# FIT2017_Uno_Shield.net
KiCad netlist of a schematic drawn in Altium Designer
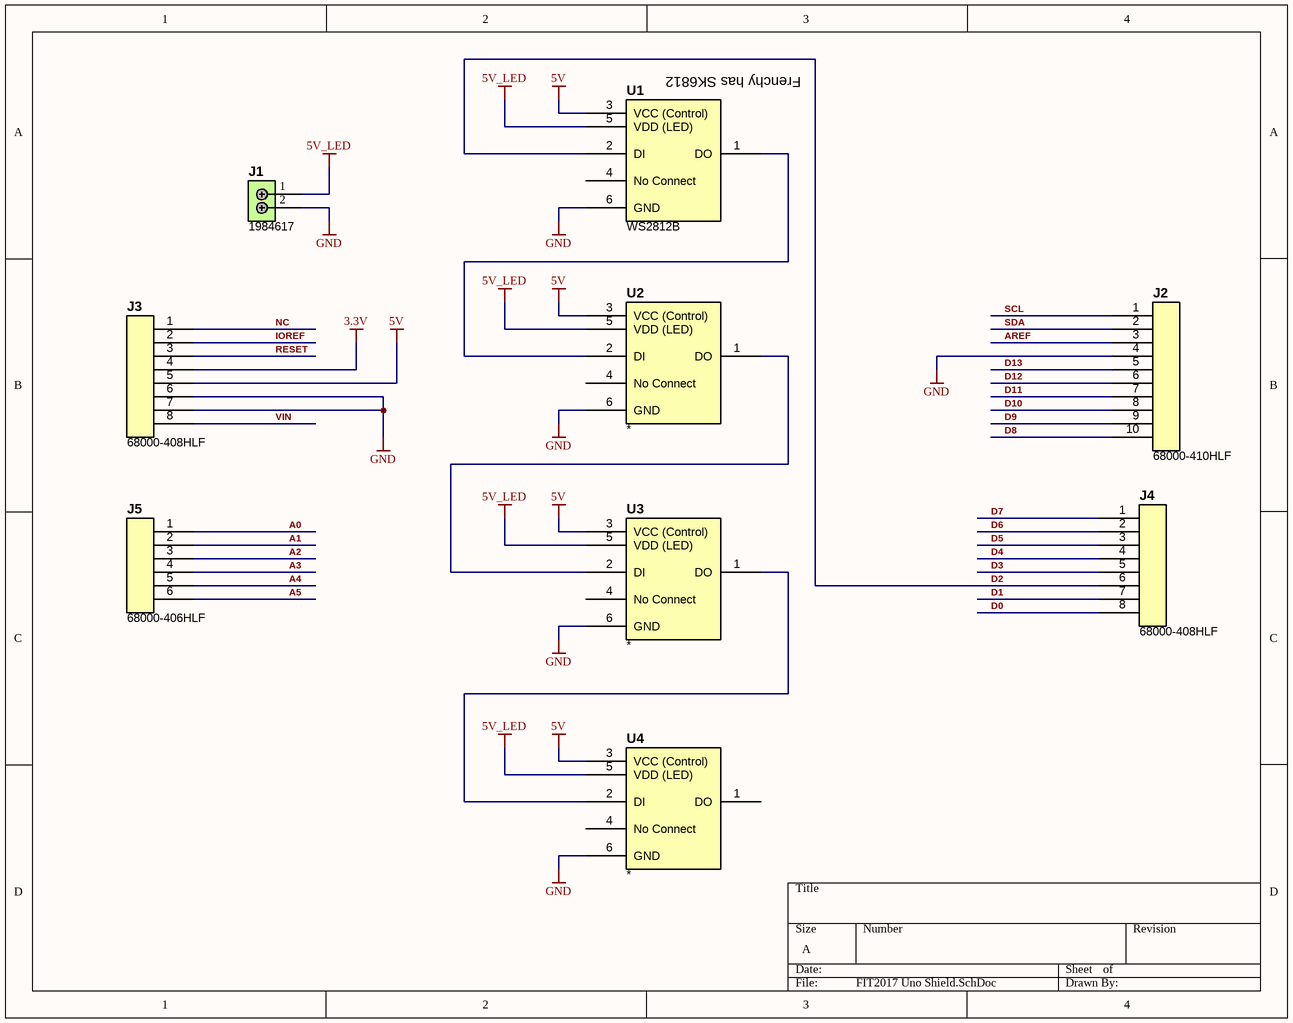
[diagram p0: FIT2017 Uno Shield.SchDoc]

(export (version "E")
  (design (tool "Eeschema 10.0.6"))
  (components
    (comp (ref "J1")
      (value "1984617")
      (footprint "1984617")
      (description "CONN TERM BLOCK T/H 2POS 3.5MM")
      (fields (field (name "MANUFACTURER") "Phoenix Contact") (field (name "VOLTAGE") "300V"))
      (libsource (lib "FIT2017_UnoShield") (part "1984617"))
    )
    (comp (ref "J2")
      (value "68000-410HLF")
      (footprint "68000-410HLF_Bottom Mount")
      (description "10 Positions Header, Unshrouded Connector 0.100\" (2.54mm) Through Hole Tin")
      (fields (field (name "MANUFACTURER") "Amphenol FCI"))
      (libsource (lib "FIT2017_UnoShield") (part "68000-410HLF"))
    )
    (comp (ref "J3")
      (value "68000-408HLF")
      (footprint "68000-408HLF_Bottom Mount")
      (description "CONN HEADER 8POS .100 STR TIN")
      (fields (field (name "MANUFACTURER") "Amphenol FCI"))
      (libsource (lib "FIT2017_UnoShield") (part "68000-408HLF"))
    )
    (comp (ref "J4")
      (value "68000-408HLF")
      (footprint "68000-408HLF_Bottom Mount")
      (description "CONN HEADER 8POS .100 STR TIN")
      (fields (field (name "MANUFACTURER") "Amphenol FCI"))
      (libsource (lib "") (part "68000-408HLF_1"))
    )
    (comp (ref "J5")
      (value "68000-406HLF")
      (footprint "68000-406HLF_Bottom Mount")
      (description "CONN HEADER 6POS .100 STR TIN")
      (fields (field (name "MANUFACTURER") "Amphenol FCI"))
      (libsource (lib "FIT2017_UnoShield") (part "68000-406HLF"))
    )
    (comp (ref "U1")
      (value "WS2812B")
      (footprint "WS2812")
      (libsource (lib "FIT2017_UnoShield") (part "WS2812"))
    )
    (comp (ref "U2") (value "*") (footprint "WS2812") (libsource (lib "FIT2017_UnoShield") (part "WS2812")))
    (comp (ref "U3") (value "*") (footprint "WS2812") (libsource (lib "FIT2017_UnoShield") (part "WS2812")))
    (comp (ref "U4") (value "*") (footprint "WS2812") (libsource (lib "FIT2017_UnoShield") (part "WS2812")))
  )
  (nets
    (net (code "1") (name "/A0") (class "Default")
      (node (ref "J5") (pin "1") (pinfunction "1_1") (pintype "passive"))
    )
    (net (code "2") (name "/A1") (class "Default")
      (node (ref "J5") (pin "2") (pinfunction "2_2") (pintype "passive"))
    )
    (net (code "3") (name "/A2") (class "Default")
      (node (ref "J5") (pin "3") (pinfunction "3_3") (pintype "passive"))
    )
    (net (code "4") (name "/A3") (class "Default")
      (node (ref "J5") (pin "4") (pinfunction "4_4") (pintype "passive"))
    )
    (net (code "5") (name "/A4") (class "Default")
      (node (ref "J5") (pin "5") (pinfunction "5_5") (pintype "passive"))
    )
    (net (code "6") (name "/A5") (class "Default")
      (node (ref "J5") (pin "6") (pinfunction "6_6") (pintype "passive"))
    )
    (net (code "7") (name "/AREF") (class "Default")
      (node (ref "J2") (pin "3") (pinfunction "3_3") (pintype "passive"))
    )
    (net (code "8") (name "/D0") (class "Default")
      (node (ref "J4") (pin "8") (pinfunction "8_8") (pintype "passive"))
    )
    (net (code "9") (name "/D1") (class "Default")
      (node (ref "J4") (pin "7") (pinfunction "7_7") (pintype "passive"))
    )
    (net (code "10") (name "/D2") (class "Default")
      (node (ref "J4") (pin "6") (pinfunction "6_6") (pintype "passive"))
      (node (ref "U1") (pin "2") (pinfunction "DI_2") (pintype "passive"))
    )
    (net (code "11") (name "/D3") (class "Default")
      (node (ref "J4") (pin "5") (pinfunction "5_5") (pintype "passive"))
    )
    (net (code "12") (name "/D4") (class "Default")
      (node (ref "J4") (pin "4") (pinfunction "4_4") (pintype "passive"))
    )
    (net (code "13") (name "/D5") (class "Default")
      (node (ref "J4") (pin "3") (pinfunction "3_3") (pintype "passive"))
    )
    (net (code "14") (name "/D6") (class "Default")
      (node (ref "J4") (pin "2") (pinfunction "2_2") (pintype "passive"))
    )
    (net (code "15") (name "/D7") (class "Default")
      (node (ref "J4") (pin "1") (pinfunction "1_1") (pintype "passive"))
    )
    (net (code "16") (name "/D8") (class "Default")
      (node (ref "J2") (pin "10") (pinfunction "10_10") (pintype "passive"))
    )
    (net (code "17") (name "/D9") (class "Default")
      (node (ref "J2") (pin "9") (pinfunction "9_9") (pintype "passive"))
    )
    (net (code "18") (name "/D10") (class "Default")
      (node (ref "J2") (pin "8") (pinfunction "8_8") (pintype "passive"))
    )
    (net (code "19") (name "/D11") (class "Default")
      (node (ref "J2") (pin "7") (pinfunction "7_7") (pintype "passive"))
    )
    (net (code "20") (name "/D12") (class "Default")
      (node (ref "J2") (pin "6") (pinfunction "6_6") (pintype "passive"))
    )
    (net (code "21") (name "/D13") (class "Default")
      (node (ref "J2") (pin "5") (pinfunction "5_5") (pintype "passive"))
    )
    (net (code "22") (name "/IOREF") (class "Default")
      (node (ref "J3") (pin "2") (pinfunction "2_2") (pintype "passive"))
    )
    (net (code "23") (name "/NC") (class "Default")
      (node (ref "J3") (pin "1") (pinfunction "1_1") (pintype "passive"))
    )
    (net (code "24") (name "/RESET") (class "Default")
      (node (ref "J3") (pin "3") (pinfunction "3_3") (pintype "passive"))
    )
    (net (code "25") (name "/SCL") (class "Default")
      (node (ref "J2") (pin "1") (pinfunction "1_1") (pintype "passive"))
    )
    (net (code "26") (name "/SDA") (class "Default")
      (node (ref "J2") (pin "2") (pinfunction "2_2") (pintype "passive"))
    )
    (net (code "27") (name "/VIN") (class "Default")
      (node (ref "J3") (pin "8") (pinfunction "8_8") (pintype "passive"))
    )
    (net (code "28") (name "3.3V") (class "Default")
      (node (ref "J3") (pin "4") (pinfunction "4_4") (pintype "passive"))
    )
    (net (code "29") (name "5V") (class "Default")
      (node (ref "J3") (pin "5") (pinfunction "5_5") (pintype "passive"))
      (node (ref "U1") (pin "3") (pinfunction "VCC_(Control)_3") (pintype "passive"))
      (node (ref "U2") (pin "3") (pinfunction "VCC_(Control)_3") (pintype "passive"))
      (node (ref "U3") (pin "3") (pinfunction "VCC_(Control)_3") (pintype "passive"))
      (node (ref "U4") (pin "3") (pinfunction "VCC_(Control)_3") (pintype "passive"))
    )
    (net (code "30") (name "5V_LED") (class "Default")
      (node (ref "J1") (pin "1") (pinfunction "1_1") (pintype "passive"))
      (node (ref "U1") (pin "5") (pinfunction "VDD_(LED)_5") (pintype "passive"))
      (node (ref "U2") (pin "5") (pinfunction "VDD_(LED)_5") (pintype "passive"))
      (node (ref "U3") (pin "5") (pinfunction "VDD_(LED)_5") (pintype "passive"))
      (node (ref "U4") (pin "5") (pinfunction "VDD_(LED)_5") (pintype "passive"))
    )
    (net (code "31") (name "GND") (class "Default")
      (node (ref "J1") (pin "2") (pinfunction "2_2") (pintype "passive"))
      (node (ref "J2") (pin "4") (pinfunction "4_4") (pintype "passive"))
      (node (ref "J3") (pin "6") (pinfunction "6_6") (pintype "passive"))
      (node (ref "J3") (pin "7") (pinfunction "7_7") (pintype "passive"))
      (node (ref "U1") (pin "6") (pinfunction "GND_6") (pintype "passive"))
      (node (ref "U2") (pin "6") (pinfunction "GND_6") (pintype "passive"))
      (node (ref "U3") (pin "6") (pinfunction "GND_6") (pintype "passive"))
      (node (ref "U4") (pin "6") (pinfunction "GND_6") (pintype "passive"))
    )
    (net (code "32") (name "Net-(U1-DO)") (class "Default")
      (node (ref "U1") (pin "1") (pinfunction "DO_1") (pintype "passive"))
      (node (ref "U2") (pin "2") (pinfunction "DI_2") (pintype "passive"))
    )
    (net (code "33") (name "Net-(U2-DO)") (class "Default")
      (node (ref "U2") (pin "1") (pinfunction "DO_1") (pintype "passive"))
      (node (ref "U3") (pin "2") (pinfunction "DI_2") (pintype "passive"))
    )
    (net (code "34") (name "Net-(U3-DO)") (class "Default")
      (node (ref "U3") (pin "1") (pinfunction "DO_1") (pintype "passive"))
      (node (ref "U4") (pin "2") (pinfunction "DI_2") (pintype "passive"))
    )
    (net (code "35") (name "unconnected-(U1-No_Connect-Pad4)") (class "Default")
      (node (ref "U1") (pin "4") (pinfunction "No_Connect_4") (pintype "passive"))
    )
    (net (code "36") (name "unconnected-(U2-No_Connect-Pad4)") (class "Default")
      (node (ref "U2") (pin "4") (pinfunction "No_Connect_4") (pintype "passive"))
    )
    (net (code "37") (name "unconnected-(U3-No_Connect-Pad4)") (class "Default")
      (node (ref "U3") (pin "4") (pinfunction "No_Connect_4") (pintype "passive"))
    )
    (net (code "38") (name "unconnected-(U4-DO-Pad1)") (class "Default")
      (node (ref "U4") (pin "1") (pinfunction "DO_1") (pintype "passive"))
    )
    (net (code "39") (name "unconnected-(U4-No_Connect-Pad4)") (class "Default")
      (node (ref "U4") (pin "4") (pinfunction "No_Connect_4") (pintype "passive"))
    )
  )
)
